# MiniHeating.net
KiCad netlist of a schematic drawn in Altium Designer
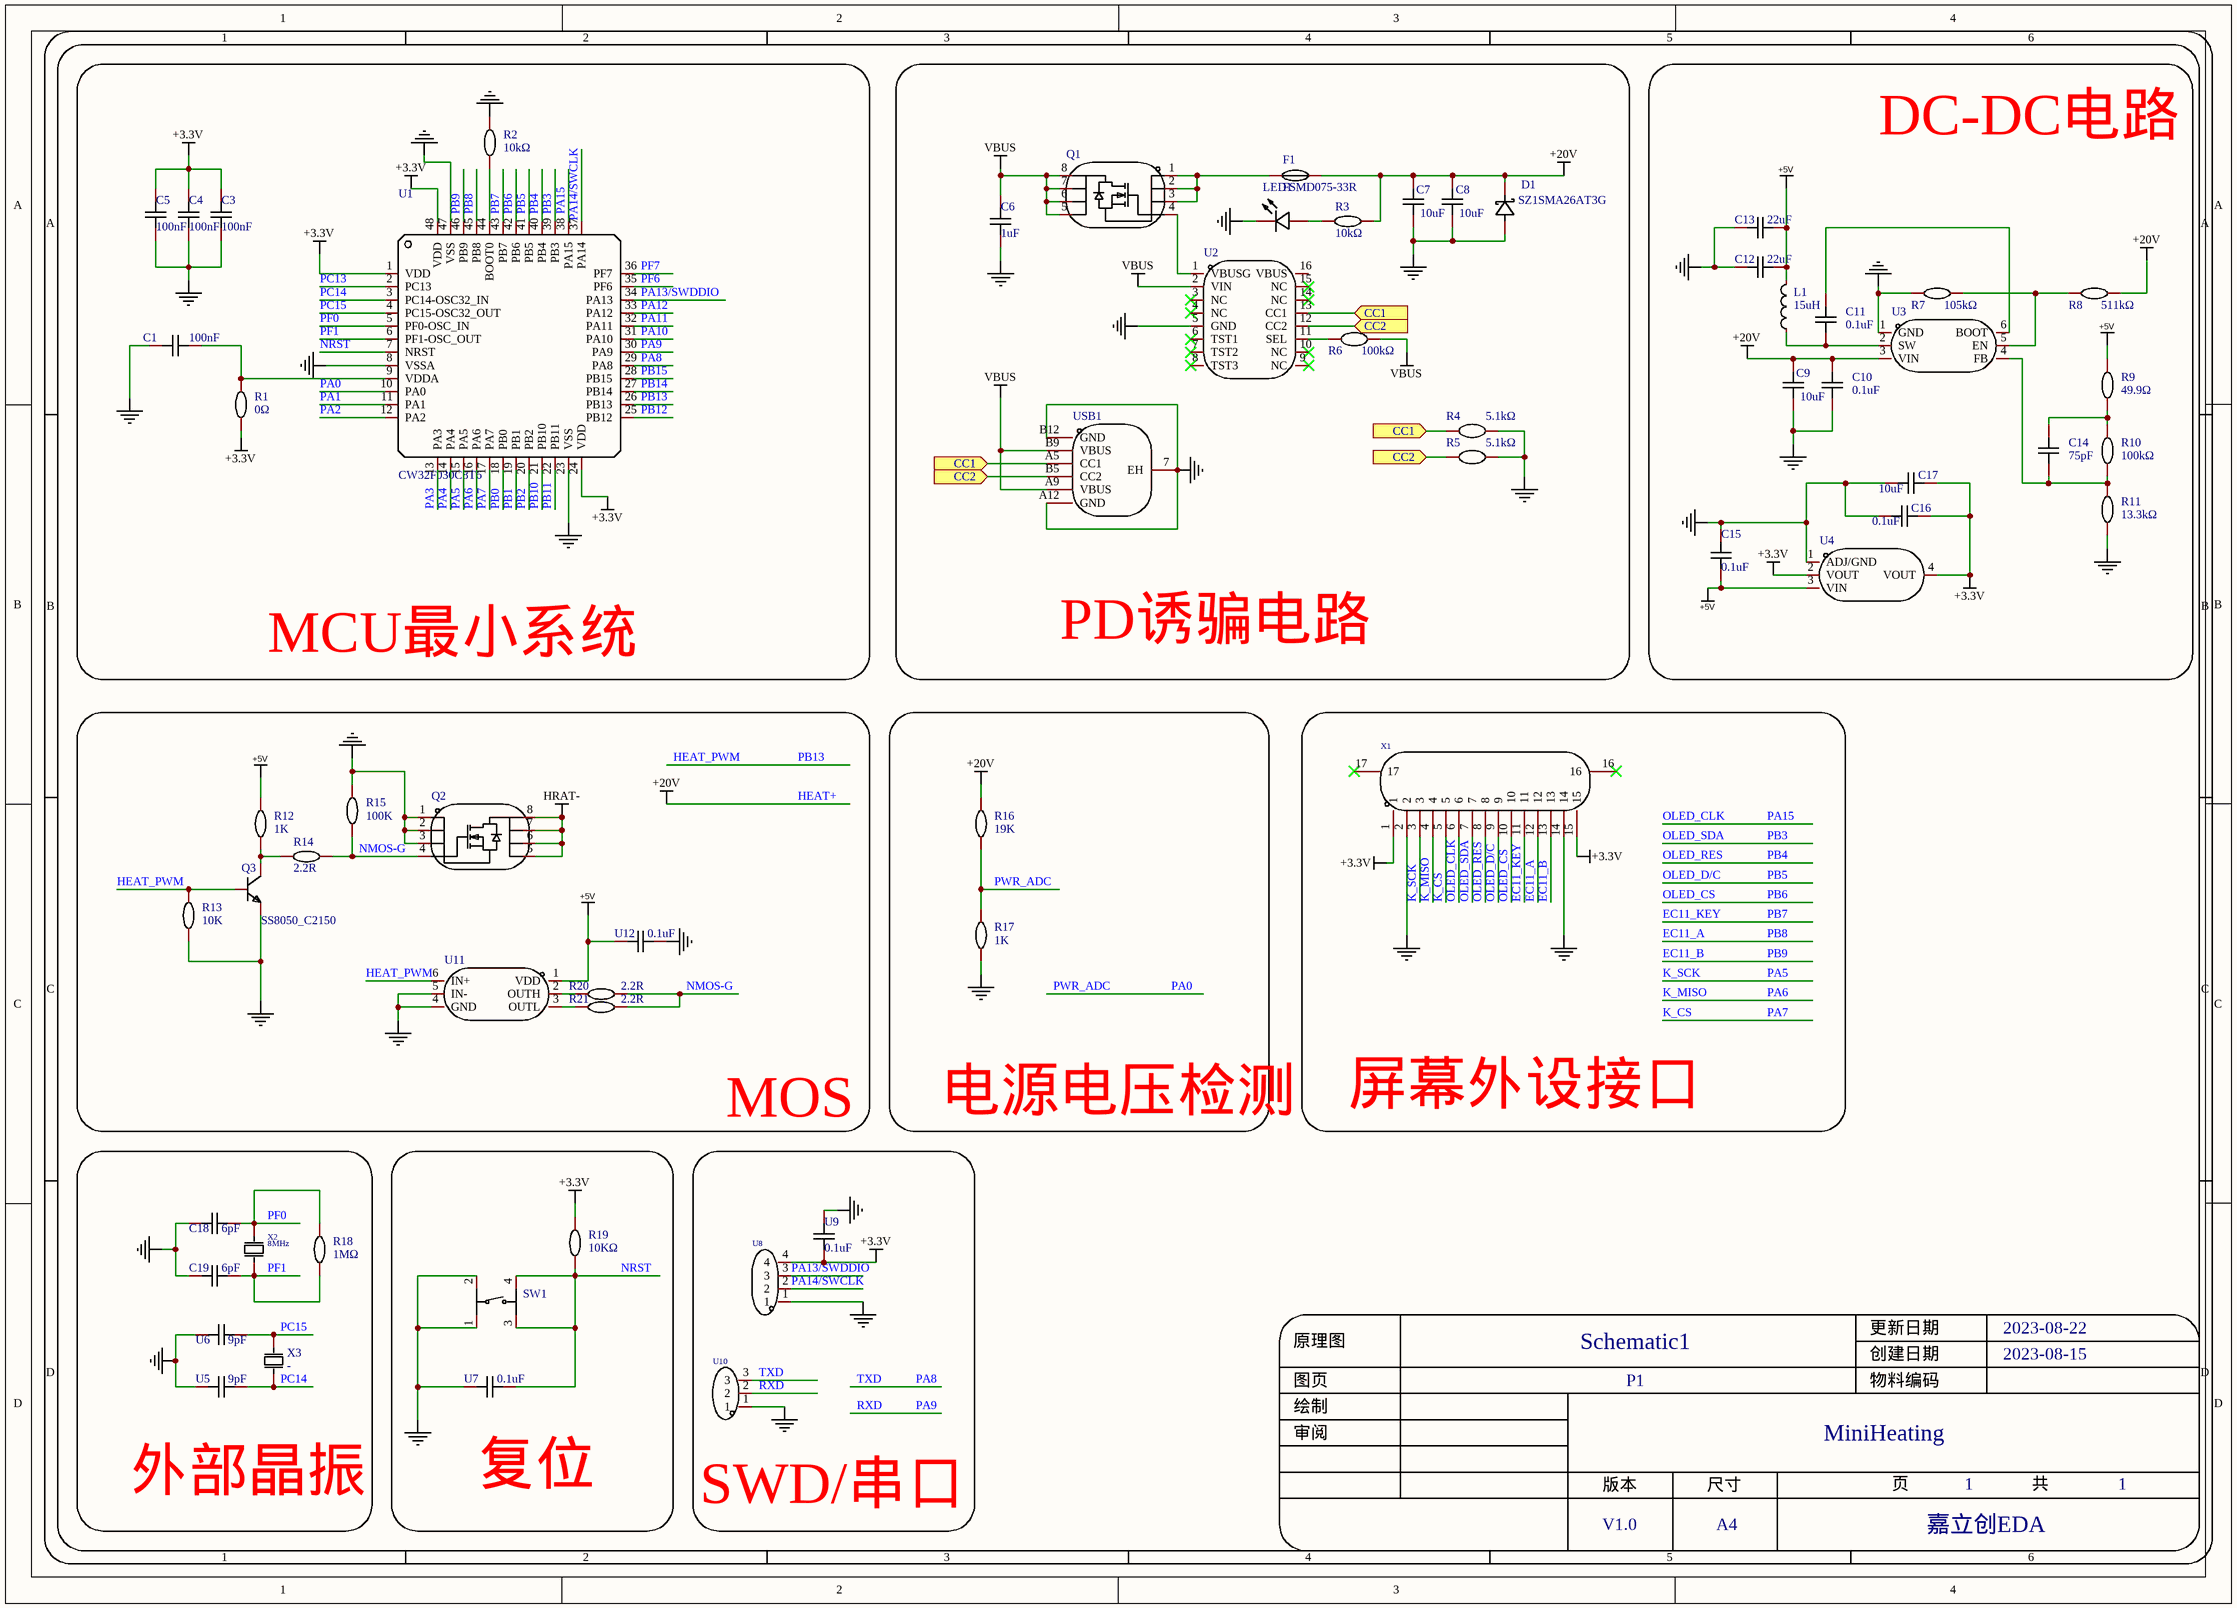
[diagram p0: MiniHeating.SchDoc]

(export (version "E")
  (design (tool "Eeschema 10.0.6"))
  (components
    (comp (ref "C1")
      (value "100nF")
      (footprint "C0603")
      (description "容值:100nF;精度:±10%;额定电压:50V;材质(温度系数):X7R;")
      (fields
        (field (name "MANUFACTURER") "YAGEO(国巨)")
        (field (name "MANUFACTURER PART") "CC0603KRX7R9BB104")
      )
      (libsource (lib "altium-import") (part "root_0_CC0603KRX7R9BB104_"))
    )
    (comp (ref "C3")
      (value "100nF")
      (footprint "C0603")
      (description "容值:100nF;精度:±10%;额定电压:50V;材质(温度系数):X7R;")
      (fields
        (field (name "MANUFACTURER") "YAGEO(国巨)")
        (field (name "MANUFACTURER PART") "CC0603KRX7R9BB104")
      )
      (libsource (lib "altium-import") (part "root_1_CC0603KRX7R9BB104_"))
    )
    (comp (ref "C4")
      (value "100nF")
      (footprint "C0603")
      (description "容值:100nF;精度:±10%;额定电压:50V;材质(温度系数):X7R;")
      (fields
        (field (name "MANUFACTURER") "YAGEO(国巨)")
        (field (name "MANUFACTURER PART") "CC0603KRX7R9BB104")
      )
      (libsource (lib "altium-import") (part "root_1_CC0603KRX7R9BB104_"))
    )
    (comp (ref "C5")
      (value "100nF")
      (footprint "C0603")
      (description "容值:100nF;精度:±10%;额定电压:50V;材质(温度系数):X7R;")
      (fields
        (field (name "MANUFACTURER") "YAGEO(国巨)")
        (field (name "MANUFACTURER PART") "CC0603KRX7R9BB104")
      )
      (libsource (lib "altium-import") (part "root_1_CC0603KRX7R9BB104_"))
    )
    (comp (ref "C6")
      (value "1uF")
      (footprint "C0805")
      (description "容值:10uF;精度:±20%;额定电压:16V;材质(温度系数):-;")
      (fields (field (name "MANUFACTURER") "SAMSUNG(三星)") (field (name "MANUFACTURER PART") "10uF"))
      (libsource (lib "altium-import") (part "root_0_10uF_C15415_"))
    )
    (comp (ref "C7")
      (value "10uF")
      (footprint "C0805")
      (description "容值:10uF;精度:±10%;额定电压:-;材质(温度系数):-;")
      (fields
        (field (name "NAME") "10uF")
        (field (name "MANUFACTURER") "muRata(村田)")
        (field (name "MANUFACTURER PART") "GRT21BC71E106KE13L")
      )
      (libsource (lib "altium-import") (part "root_1_GRT21BC71E106KE13L_"))
    )
    (comp (ref "C8")
      (value "10uF")
      (footprint "C0805")
      (description "容值:10uF;精度:±10%;额定电压:-;材质(温度系数):-;")
      (fields
        (field (name "NAME") "10uF")
        (field (name "MANUFACTURER") "muRata(村田)")
        (field (name "MANUFACTURER PART") "GRT21BC71E106KE13L")
      )
      (libsource (lib "altium-import") (part "root_1_GRT21BC71E106KE13L_"))
    )
    (comp (ref "C9")
      (value "10uF")
      (footprint "C0805")
      (description "容值:10uF;精度:±10%;额定电压:-;材质(温度系数):-;")
      (fields
        (field (name "NAME") "10uF")
        (field (name "MANUFACTURER") "muRata(村田)")
        (field (name "MANUFACTURER PART") "GRT21BC71E106KE13L")
      )
      (libsource (lib "altium-import") (part "root_1_GRT21BC71E106KE13L_"))
    )
    (comp (ref "C10")
      (value "0.1uF")
      (footprint "C0603")
      (description "容值:0.1uF;精度:±10%;额定电压:50V;温度系数:-;")
      (fields
        (field (name "MANUFACTURER") "Knowles(楼氏)")
        (field (name "MANUFACTURER PART") "0603BB104K500NGT")
      )
      (libsource (lib "altium-import") (part "root_1_0603BB104K500NGT_"))
    )
    (comp (ref "C11")
      (value "0.1uF")
      (footprint "C0603")
      (description "容值:0.1uF;精度:±10%;额定电压:50V;温度系数:-;")
      (fields
        (field (name "MANUFACTURER") "Knowles(楼氏)")
        (field (name "MANUFACTURER PART") "0603BB104K500NGT")
      )
      (libsource (lib "altium-import") (part "root_3_0603BB104K500NGT_"))
    )
    (comp (ref "C12")
      (value "22uF")
      (footprint "C0805")
      (description "容值:10uF;精度:±10%;额定电压:-;材质(温度系数):-;")
      (fields
        (field (name "NAME") "22uF")
        (field (name "MANUFACTURER") "muRata(村田)")
        (field (name "MANUFACTURER PART") "GRT21BC71E106KE13L")
      )
      (libsource (lib "altium-import") (part "root_2_GRT21BC71E106KE13L_"))
    )
    (comp (ref "C13")
      (value "22uF")
      (footprint "C0805")
      (description "容值:10uF;精度:±10%;额定电压:-;材质(温度系数):-;")
      (fields
        (field (name "NAME") "22uF")
        (field (name "MANUFACTURER") "muRata(村田)")
        (field (name "MANUFACTURER PART") "GRT21BC71E106KE13L")
      )
      (libsource (lib "altium-import") (part "root_2_GRT21BC71E106KE13L_"))
    )
    (comp (ref "C14")
      (value "75pF")
      (footprint "C0603")
      (description "容值:0.1uF;精度:±10%;额定电压:50V;温度系数:-;")
      (fields
        (field (name "MANUFACTURER") "Knowles(楼氏)")
        (field (name "MANUFACTURER PART") "0603BB104K500NGT")
      )
      (libsource (lib "altium-import") (part "root_1_0603BB104K500NGT_"))
    )
    (comp (ref "C15")
      (value "0.1uF")
      (footprint "C0603")
      (description "容值:0.1uF;精度:±10%;额定电压:50V;温度系数:-;")
      (fields
        (field (name "MANUFACTURER") "Knowles(楼氏)")
        (field (name "MANUFACTURER PART") "0603BB104K500NGT")
      )
      (libsource (lib "altium-import") (part "root_1_0603BB104K500NGT_"))
    )
    (comp (ref "C16")
      (value "0.1uF")
      (footprint "C0603")
      (description "容值:0.1uF;精度:±10%;额定电压:50V;温度系数:-;")
      (fields
        (field (name "MANUFACTURER") "Knowles(楼氏)")
        (field (name "MANUFACTURER PART") "0603BB104K500NGT")
      )
      (libsource (lib "altium-import") (part "root_2_0603BB104K500NGT_"))
    )
    (comp (ref "C17")
      (value "10uF")
      (footprint "C0805")
      (description "容值:10uF;精度:±10%;额定电压:-;材质(温度系数):-;")
      (fields
        (field (name "NAME") "10uF")
        (field (name "MANUFACTURER") "muRata(村田)")
        (field (name "MANUFACTURER PART") "GRT21BC71E106KE13L")
      )
      (libsource (lib "altium-import") (part "root_2_GRT21BC71E106KE13L_"))
    )
    (comp (ref "C18")
      (value "6pF")
      (footprint "C0603")
      (description "容值:6pF;额定电压:50V;材质(温度系数):C0G;")
      (fields (field (name "MANUFACTURER") "TDK") (field (name "MANUFACTURER PART") "CGA3E2C0G1H060DT0Y0N"))
      (libsource (lib "altium-import") (part "root_0_CGA3E2C0G1H060DT0Y0N_"))
    )
    (comp (ref "C19")
      (value "6pF")
      (footprint "C0603")
      (description "容值:6pF;额定电压:50V;材质(温度系数):C0G;")
      (fields (field (name "MANUFACTURER") "TDK") (field (name "MANUFACTURER PART") "CGA3E2C0G1H060DT0Y0N"))
      (libsource (lib "altium-import") (part "root_0_CGA3E2C0G1H060DT0Y0N_"))
    )
    (comp (ref "D1")
      (value "SZ1SMA26AT3G")
      (footprint "SMA_L4.3-W2.6-LS5.2-FD")
      (fields (field (name "NAME") "SZ1SMA26AT3G") (field (name "MANUFACTURER") "Littelfuse(美国力特)"))
      (libsource (lib "altium-import") (part "root_3_SZ1SMA26AT3G_"))
    )
    (comp (ref "F1")
      (value "FSMD075-33R")
      (footprint "F1812")
      (description "最大电压:33V;最大电流:40A;保持电流:750mA;跳闸电流:1.5A;")
      (fields (field (name "NAME") "FSMD075-33R") (field (name "MANUFACTURER") "FUZETEC(台湾富致)"))
      (libsource (lib "altium-import") (part "root_0_FSMD075-33R_"))
    )
    (comp (ref "L1")
      (value "15uH")
      (footprint "IND-SMD_L7.0-W6.6_FXL0630")
      (description "电感值:15uH;精度:±20%;额定电流:3A;饱和电流(Isat):4.5A;")
      (fields (field (name "MANUFACTURER") "cjiang(长江微电)") (field (name "MANUFACTURER PART") "FXL0630-150-M"))
      (libsource (lib "altium-import") (part "root_1_FXL0630-150-M_"))
    )
    (comp (ref "LED1")
      (value "KT-0603R")
      (footprint "LED0603-RD")
      (description "发光颜色:红灯;二极管配置:-;透镜颜色:-;主波长:-;色温:-;功率:-;发光角度:-;安装方式:-;工作温度:-40℃~+85℃;")
      (fields (field (name "MANUFACTURER") "KENTO"))
      (libsource (lib "altium-import") (part "root_0_KT-0603R_"))
    )
    (comp (ref "Q1")
      (value "BSC123N08NS3 G")
      (footprint "PG-TDSON-8_L5.0-W6.0-P1.27-BL-EP")
      (libsource (lib "altium-import") (part "root_0_mirrored_BSC123N08NS3 G_"))
    )
    (comp (ref "Q2")
      (value "BSC123N08NS3 G")
      (footprint "PG-TDSON-8_L5.0-W6.0-P1.27-BL-EP")
      (libsource (lib "altium-import") (part "root_0_BSC123N08NS3 G_"))
    )
    (comp (ref "Q3")
      (value "SS8050_C2150")
      (footprint "SOT-23-3_L2.9-W1.3-P1.90-LS2.4-BR")
      (description "晶体管类型:NPN;集射极击穿电压(Vceo):25V;集电极电流(Ic):1.5A;功率(Pd):300mW;直流电流增益(hFE@Ic,Vce):200@100mA,1V;")
      (fields
        (field (name "DEVICE") "SS8050_C2150")
        (field (name "MANUFACTURER") "CJ(江苏长电/长晶)")
        (field (name "MANUFACTURER PART") "SS8050")
      )
      (libsource (lib "altium-import") (part "root_0_SS8050_C2150_"))
    )
    (comp (ref "R1")
      (value "0Ω")
      (footprint "R0603")
      (description "电阻类型:厚膜电阻;阻值:470kΩ;精度:±1%;功率:100mW;")
      (fields
        (field (name "MANUFACTURER") "UNI-ROYAL(厚声)")
        (field (name "MANUFACTURER PART") "0603WAF4703T5E")
      )
      (libsource (lib "altium-import") (part "root_1_0603WAF4703T5E_"))
    )
    (comp (ref "R2")
      (value "10kΩ")
      (footprint "R0603")
      (description "电阻类型:厚膜电阻;阻值:24kΩ;精度:±1%;功率:100mW;")
      (fields
        (field (name "MANUFACTURER") "UNI-ROYAL(厚声)")
        (field (name "MANUFACTURER PART") "0603WAF2402T5E")
      )
      (libsource (lib "altium-import") (part "root_1_0603WAF2402T5E_"))
    )
    (comp (ref "R3")
      (value "10kΩ")
      (footprint "R0603")
      (description "电阻类型:薄膜电阻;阻值:10kΩ;精度:±0.1%;功率:63mW;")
      (fields
        (field (name "MANUFACTURER") "SEI(Stackpole Electronics Inc.)")
        (field (name "MANUFACTURER PART") "RNCS0603BKE10K0")
      )
      (libsource (lib "altium-import") (part "root_2_RNCS0603BKE10K0_"))
    )
    (comp (ref "R4")
      (value "5.1kΩ")
      (footprint "R0603")
      (description "电阻类型:厚膜电阻;阻值:10kΩ;精度:±0.5%;功率:100mW;")
      (fields (field (name "MANUFACTURER") "YAGEO(国巨)") (field (name "MANUFACTURER PART") "AC0603DR-0710KL"))
      (libsource (lib "altium-import") (part "root_0_AC0603DR-0710KL_"))
    )
    (comp (ref "R5")
      (value "5.1kΩ")
      (footprint "R0603")
      (description "电阻类型:厚膜电阻;阻值:10kΩ;精度:±0.5%;功率:100mW;")
      (fields (field (name "MANUFACTURER") "YAGEO(国巨)") (field (name "MANUFACTURER PART") "AC0603DR-0710KL"))
      (libsource (lib "altium-import") (part "root_0_AC0603DR-0710KL_"))
    )
    (comp (ref "R6")
      (value "100kΩ")
      (footprint "R0603")
      (description "阻值:100kΩ;功率:125mW;")
      (fields
        (field (name "NAME") "100kΩ")
        (field (name "MANUFACTURER") "Milliohm(毫欧)")
        (field (name "MANUFACTURER PART") "HoLTT0805-1/8W-100K-5%")
      )
      (libsource (lib "altium-import") (part "root_0_HoLTT0805-1/8W-100K-5%_"))
    )
    (comp (ref "R7")
      (value "105kΩ")
      (footprint "R0603")
      (description "电阻类型:厚膜电阻;阻值:105kΩ;精度:±1%;功率:100mW;")
      (fields (field (name "MANUFACTURER") "YAGEO(国巨)") (field (name "MANUFACTURER PART") "AC0603FR-07105KL"))
      (libsource (lib "altium-import") (part "root_0_AC0603FR-07105KL_"))
    )
    (comp (ref "R8")
      (value "511kΩ")
      (footprint "R0603")
      (description "电阻类型:厚膜电阻;阻值:105kΩ;精度:±1%;功率:100mW;")
      (fields (field (name "MANUFACTURER") "YAGEO(国巨)") (field (name "MANUFACTURER PART") "AC0603FR-07105KL"))
      (libsource (lib "altium-import") (part "root_0_AC0603FR-07105KL_"))
    )
    (comp (ref "R9")
      (value "49.9Ω")
      (footprint "R0603")
      (description "阻值:50kΩ;精度:±0.1%;功率:62.5mW;")
      (fields (field (name "MANUFACTURER") "Viking(光颉)") (field (name "MANUFACTURER PART") "AR03BTC5002A"))
      (libsource (lib "altium-import") (part "root_1_AR03BTC5002A_"))
    )
    (comp (ref "R10")
      (value "100kΩ")
      (footprint "R0603")
      (description "阻值:50kΩ;精度:±0.1%;功率:62.5mW;")
      (fields (field (name "MANUFACTURER") "Viking(光颉)") (field (name "MANUFACTURER PART") "AR03BTC5002A"))
      (libsource (lib "altium-import") (part "root_1_AR03BTC5002A_"))
    )
    (comp (ref "R11")
      (value "13.3kΩ")
      (footprint "R0603")
      (description "阻值:50kΩ;精度:±0.1%;功率:62.5mW;")
      (fields (field (name "MANUFACTURER") "Viking(光颉)") (field (name "MANUFACTURER PART") "AR03BTC5002A"))
      (libsource (lib "altium-import") (part "root_1_AR03BTC5002A_"))
    )
    (comp (ref "R12")
      (value "1K")
      (footprint "R0603")
      (description "电阻类型:厚膜电阻;阻值:470kΩ;精度:±1%;功率:100mW;")
      (fields
        (field (name "MANUFACTURER") "UNI-ROYAL(厚声)")
        (field (name "MANUFACTURER PART") "0603WAF4703T5E")
      )
      (libsource (lib "altium-import") (part "root_1_0603WAF4703T5E_"))
    )
    (comp (ref "R13")
      (value "10K")
      (footprint "R0603")
      (description "电阻类型:厚膜电阻;阻值:470kΩ;精度:±1%;功率:100mW;")
      (fields
        (field (name "MANUFACTURER") "UNI-ROYAL(厚声)")
        (field (name "MANUFACTURER PART") "0603WAF4703T5E")
      )
      (libsource (lib "altium-import") (part "root_1_0603WAF4703T5E_"))
    )
    (comp (ref "R14")
      (value "2.2R")
      (footprint "R0603")
      (description "电阻类型:厚膜电阻;阻值:470kΩ;精度:±1%;功率:100mW;")
      (fields
        (field (name "MANUFACTURER") "UNI-ROYAL(厚声)")
        (field (name "MANUFACTURER PART") "0603WAF4703T5E")
      )
      (libsource (lib "altium-import") (part "root_2_0603WAF4703T5E_"))
    )
    (comp (ref "R15")
      (value "100K")
      (footprint "R0603")
      (description "电阻类型:厚膜电阻;阻值:470kΩ;精度:±1%;功率:100mW;")
      (fields
        (field (name "MANUFACTURER") "UNI-ROYAL(厚声)")
        (field (name "MANUFACTURER PART") "0603WAF4703T5E")
      )
      (libsource (lib "altium-import") (part "root_1_0603WAF4703T5E_"))
    )
    (comp (ref "R16")
      (value "19K")
      (footprint "R0603")
      (description "电阻类型:厚膜电阻;阻值:470kΩ;精度:±1%;功率:100mW;")
      (fields
        (field (name "MANUFACTURER") "UNI-ROYAL(厚声)")
        (field (name "MANUFACTURER PART") "0603WAF4703T5E")
      )
      (libsource (lib "altium-import") (part "root_1_0603WAF4703T5E_"))
    )
    (comp (ref "R17")
      (value "1K")
      (footprint "R0603")
      (description "电阻类型:厚膜电阻;阻值:470kΩ;精度:±1%;功率:100mW;")
      (fields
        (field (name "MANUFACTURER") "UNI-ROYAL(厚声)")
        (field (name "MANUFACTURER PART") "0603WAF4703T5E")
      )
      (libsource (lib "altium-import") (part "root_1_0603WAF4703T5E_"))
    )
    (comp (ref "R18")
      (value "1MΩ")
      (footprint "R0603")
      (description "电阻类型:厚膜电阻;阻值:1MΩ;精度:±1%;功率:100mW;")
      (fields
        (field (name "MANUFACTURER") "UNI-ROYAL(厚声)")
        (field (name "MANUFACTURER PART") "0603WAF1004T5E")
      )
      (libsource (lib "altium-import") (part "root_1_0603WAF1004T5E_"))
    )
    (comp (ref "R19")
      (value "10KΩ")
      (footprint "R0603")
      (description "电阻类型:厚膜电阻;阻值:1MΩ;精度:±1%;功率:100mW;")
      (fields
        (field (name "MANUFACTURER") "UNI-ROYAL(厚声)")
        (field (name "MANUFACTURER PART") "0603WAF1004T5E")
      )
      (libsource (lib "altium-import") (part "root_1_0603WAF1004T5E_"))
    )
    (comp (ref "R20")
      (value "2.2R")
      (footprint "R0603")
      (description "电阻类型:厚膜电阻;阻值:470kΩ;精度:±1%;功率:100mW;")
      (fields
        (field (name "MANUFACTURER") "UNI-ROYAL(厚声)")
        (field (name "MANUFACTURER PART") "0603WAF4703T5E")
      )
      (libsource (lib "altium-import") (part "root_2_0603WAF4703T5E_"))
    )
    (comp (ref "R21")
      (value "2.2R")
      (footprint "R0603")
      (description "电阻类型:厚膜电阻;阻值:470kΩ;精度:±1%;功率:100mW;")
      (fields
        (field (name "MANUFACTURER") "UNI-ROYAL(厚声)")
        (field (name "MANUFACTURER PART") "0603WAF4703T5E")
      )
      (libsource (lib "altium-import") (part "root_2_0603WAF4703T5E_"))
    )
    (comp (ref "SW1")
      (value "TS-1186D-C-A")
      (footprint "SW-SMD_TS-1186D-C-A")
      (description "触点电流:50mA;额定电压(DC):12V;绝缘电阻:-;电路结构:单刀单掷;安装方式:卧贴;带灯:无;作用力:260gf;机械寿命:10万次;带支架:否;")
      (fields (field (name "MANUFACTURER") "XKB Connectivity(中国星坤)"))
      (libsource (lib "altium-import") (part "root_1_TS-1186D-C-A_"))
    )
    (comp (ref "U1")
      (value "CW32F030C8T6")
      (footprint "LQFP-48_L7.0-W7.0-P0.50-LS9.0-TL")
      (fields (field (name "NAME") "CW32F030C8T6") (field (name "MANUFACTURER") "CW(芯源)"))
      (libsource (lib "altium-import") (part "root_0_CW32F030C8T6_C3019113_"))
    )
    (comp (ref "U2")
      (value "IP2721")
      (footprint "TSSOP-16_L5.0-W4.4-P0.65-LS6.4-BL")
      (fields (field (name "MANUFACTURER") "INJOINIC(英集芯)"))
      (libsource (lib "altium-import") (part "root_0_IP2721_"))
    )
    (comp (ref "U3")
      (value "TPS54202DDCR")
      (footprint "SOT-23-6_L2.9-W1.6-P0.95-LS2.8-BL")
      (description "可输出电流:2A;开关工作频率:500kHz;输出类型:Adjustable;输出电压的路数:1;功能类型:Step-Down;输出配置:Positive;")
      (fields (field (name "MANUFACTURER") "TI(德州仪器)"))
      (libsource (lib "altium-import") (part "root_0_TPS54202DDCR_"))
    )
    (comp (ref "U4")
      (value "LM1117GS-3.3")
      (footprint "SOT-223-3_L6.5-W3.4-P2.30-LS7.0-BR")
      (description "输出类型:-;")
      (fields (field (name "MANUFACTURER") "HTC"))
      (libsource (lib "altium-import") (part "root_0_LM1117GS-3.3_"))
    )
    (comp (ref "U5")
      (value "9pF")
      (footprint "C0603")
      (description "容值:9pF;额定电压:50V;材质(温度系数):C0G;")
      (fields (field (name "MANUFACTURER") "TDK") (field (name "MANUFACTURER PART") "C1608C0G1H090D080AA"))
      (libsource (lib "altium-import") (part "root_0_C1608C0G1H090D080AA_"))
    )
    (comp (ref "U6")
      (value "9pF")
      (footprint "C0603")
      (description "容值:9pF;额定电压:50V;材质(温度系数):C0G;")
      (fields (field (name "MANUFACTURER") "TDK") (field (name "MANUFACTURER PART") "C1608C0G1H090D080AA"))
      (libsource (lib "altium-import") (part "root_0_C1608C0G1H090D080AA_"))
    )
    (comp (ref "U7")
      (value "0.1uF")
      (footprint "C0603")
      (description "容值:9pF;额定电压:50V;材质(温度系数):C0G;")
      (fields (field (name "MANUFACTURER") "TDK") (field (name "MANUFACTURER PART") "C1608C0G1H090D080AA"))
      (libsource (lib "altium-import") (part "root_0_C1608C0G1H090D080AA_"))
    )
    (comp (ref "U8")
      (value "ZX-PZ2.54-1-4PWZ")
      (footprint "HDR-TH_4P-P2.54-H-M-W10.3")
      (fields (field (name "MANUFACTURER") "Megastar(兆星)"))
      (libsource (lib "altium-import") (part "root_2_ZX-PZ2.54-1-4PWZ_"))
    )
    (comp (ref "U9")
      (value "0.1uF")
      (footprint "C0603")
      (description "容值:9pF;额定电压:50V;材质(温度系数):C0G;")
      (fields (field (name "MANUFACTURER") "TDK") (field (name "MANUFACTURER PART") "C1608C0G1H090D080AA"))
      (libsource (lib "altium-import") (part "root_1_C1608C0G1H090D080AA_"))
    )
    (comp (ref "U10")
      (value "ZX-PZ2.54-1-3PZZ")
      (footprint "HDR-TH_3P-P2.54-V-M-1")
      (fields (field (name "MANUFACTURER") "Megastar(兆星)"))
      (libsource (lib "altium-import") (part "root_2_ZX-PZ2.54-1-3PZZ_"))
    )
    (comp (ref "U11")
      (value "UCC27511DBVR")
      (footprint "SOT-23-6_L2.9-W1.6-P0.95-LS2.8-BL")
      (description "驱动配置:低边;负载类型:MOSFET；IGBT;电源电压:4.5V~18V;峰值灌电流:8A;峰值拉电流:4A;")
      (fields (field (name "MANUFACTURER") "TI(德州仪器)"))
      (libsource (lib "altium-import") (part "root_0_mirrored_UCC27511DBVR_"))
    )
    (comp (ref "U12")
      (value "0.1uF")
      (footprint "C0603")
      (description "容值:9pF;额定电压:50V;材质(温度系数):C0G;")
      (fields (field (name "MANUFACTURER") "TDK") (field (name "MANUFACTURER PART") "C1608C0G1H090D080AA"))
      (libsource (lib "altium-import") (part "root_0_C1608C0G1H090D080AA_"))
    )
    (comp (ref "USB1")
      (value "TYPE-C-6P-DIP2X2")
      (footprint "TYPE-C-SMD_TYPE-C-6P")
      (libsource (lib "altium-import") (part "root_0_TYPE-C-6P-DIP2X2_"))
    )
    (comp (ref "X1")
      (value "AFC01-S15FCA-00")
      (footprint "FPC-SMD_15P-P0.50_JS_AFC01-S15FCA-00")
      (description "间距:0.5mm;触点数量:15;锁定特性:翻盖式;安装类型:卧贴;触点类型:下接;工作温度范围:-;")
      (fields (field (name "MANUFACTURER") "JS(钜硕电子)"))
      (libsource (lib "altium-import") (part "root_1_AFC01-S15FCA-00_"))
    )
    (comp (ref "X2")
      (value "8MHz")
      (footprint "HC-49US_L11.5-W4.5-P4.88")
      (description "频率:8MHz;频率公差:±30ppm;负载电容:20pF;")
      (fields (field (name "MANUFACTURER") "TAE(雅晶鑫)") (field (name "MANUFACTURER PART") "TAXD8M2GLFBET2T"))
      (libsource (lib "altium-import") (part "root_1_TAXD8M2GLFBET2T_"))
    )
    (comp (ref "X3")
      (value "-")
      (footprint "OSC-SMD_L3.2-W1.5")
      (description "频率:-;负载电容:-;")
      (fields (field (name "MANUFACTURER") "TKD(泰晶)") (field (name "MANUFACTURER PART") "SF32WK32768D31T002"))
      (libsource (lib "altium-import") (part "root_1_SF32WK32768D31T002_"))
    )
  )
  (nets
    (net (code "1") (name "+3.3V") (class "Default")
      (node (ref "C16") (pin "1") (pinfunction "1_1") (pintype "passive"))
      (node (ref "C17") (pin "1") (pinfunction "1_1") (pintype "passive"))
      (node (ref "C3") (pin "2") (pinfunction "2_2") (pintype "passive"))
      (node (ref "C4") (pin "2") (pinfunction "2_2") (pintype "passive"))
      (node (ref "C5") (pin "2") (pinfunction "2_2") (pintype "passive"))
      (node (ref "R1") (pin "1") (pinfunction "1_1") (pintype "passive"))
      (node (ref "R19") (pin "2") (pinfunction "2_2") (pintype "passive"))
      (node (ref "U1") (pin "1") (pinfunction "VDD_1") (pintype "passive"))
      (node (ref "U1") (pin "24") (pinfunction "VDD_24") (pintype "passive"))
      (node (ref "U1") (pin "48") (pinfunction "VDD_48") (pintype "passive"))
      (node (ref "U4") (pin "2") (pinfunction "VOUT_2") (pintype "passive"))
      (node (ref "U4") (pin "4") (pinfunction "VOUT_4") (pintype "passive"))
      (node (ref "U8") (pin "4") (pinfunction "4_4") (pintype "passive"))
      (node (ref "U9") (pin "1") (pinfunction "1_1") (pintype "passive"))
      (node (ref "X1") (pin "1") (pinfunction "1_1") (pintype "passive"))
      (node (ref "X1") (pin "15") (pinfunction "15_15") (pintype "passive"))
    )
    (net (code "2") (name "+5V") (class "Default")
      (node (ref "C12") (pin "1") (pinfunction "1_1") (pintype "passive"))
      (node (ref "C13") (pin "1") (pinfunction "1_1") (pintype "passive"))
      (node (ref "C15") (pin "1") (pinfunction "1_1") (pintype "passive"))
      (node (ref "L1") (pin "2") (pinfunction "2_2") (pintype "passive"))
      (node (ref "R12") (pin "2") (pinfunction "2_2") (pintype "passive"))
      (node (ref "R9") (pin "2") (pinfunction "2_2") (pintype "passive"))
      (node (ref "U11") (pin "1") (pinfunction "VDD_1") (pintype "passive"))
      (node (ref "U12") (pin "1") (pinfunction "1_1") (pintype "passive"))
      (node (ref "U4") (pin "3") (pinfunction "VIN_3") (pintype "passive"))
    )
    (net (code "3") (name "+20V") (class "Default")
      (node (ref "C10") (pin "2") (pinfunction "2_2") (pintype "passive"))
      (node (ref "C7") (pin "2") (pinfunction "2_2") (pintype "passive"))
      (node (ref "C8") (pin "2") (pinfunction "2_2") (pintype "passive"))
      (node (ref "C9") (pin "2") (pinfunction "2_2") (pintype "passive"))
      (node (ref "D1") (pin "2") (pinfunction "K_2") (pintype "passive"))
      (node (ref "F1") (pin "2") (pinfunction "2_2") (pintype "passive"))
      (node (ref "R16") (pin "2") (pinfunction "2_2") (pintype "passive"))
      (node (ref "R3") (pin "1") (pinfunction "1_1") (pintype "passive"))
      (node (ref "R8") (pin "2") (pinfunction "2_2") (pintype "passive"))
      (node (ref "U3") (pin "3") (pinfunction "VIN_3") (pintype "passive"))
    )
    (net (code "4") (name "/CC1") (class "Default")
      (node (ref "R4") (pin "1") (pinfunction "1_1") (pintype "passive"))
      (node (ref "U2") (pin "13") (pinfunction "CC1_13") (pintype "passive"))
      (node (ref "USB1") (pin "A5") (pinfunction "CC1_A5") (pintype "passive"))
    )
    (net (code "5") (name "/CC2") (class "Default")
      (node (ref "R5") (pin "1") (pinfunction "1_1") (pintype "passive"))
      (node (ref "U2") (pin "12") (pinfunction "CC2_12") (pintype "passive"))
      (node (ref "USB1") (pin "B5") (pinfunction "CC2_B5") (pintype "passive"))
    )
    (net (code "6") (name "/EC11_A") (class "Default")
      (node (ref "U1") (pin "45") (pinfunction "PB8_45") (pintype "passive"))
      (node (ref "X1") (pin "12") (pinfunction "12_12") (pintype "passive"))
    )
    (net (code "7") (name "/EC11_B") (class "Default")
      (node (ref "U1") (pin "46") (pinfunction "PB9_46") (pintype "passive"))
      (node (ref "X1") (pin "13") (pinfunction "13_13") (pintype "passive"))
    )
    (net (code "8") (name "/EC11_KEY") (class "Default")
      (node (ref "U1") (pin "43") (pinfunction "PB7_43") (pintype "passive"))
      (node (ref "X1") (pin "11") (pinfunction "11_11") (pintype "passive"))
    )
    (net (code "9") (name "/HEAT_PWM") (class "Default")
      (node (ref "Q3") (pin "1") (pinfunction "B_1") (pintype "passive"))
      (node (ref "R13") (pin "2") (pinfunction "2_2") (pintype "passive"))
      (node (ref "U1") (pin "26") (pinfunction "PB13_26") (pintype "passive"))
      (node (ref "U11") (pin "6") (pinfunction "IN+_6") (pintype "passive"))
    )
    (net (code "10") (name "/K_CS") (class "Default")
      (node (ref "U1") (pin "17") (pinfunction "PA7_17") (pintype "passive"))
      (node (ref "X1") (pin "5") (pinfunction "5_5") (pintype "passive"))
    )
    (net (code "11") (name "/K_MISO") (class "Default")
      (node (ref "U1") (pin "16") (pinfunction "PA6_16") (pintype "passive"))
      (node (ref "X1") (pin "4") (pinfunction "4_4") (pintype "passive"))
    )
    (net (code "12") (name "/K_SCK") (class "Default")
      (node (ref "U1") (pin "15") (pinfunction "PA5_15") (pintype "passive"))
      (node (ref "X1") (pin "3") (pinfunction "3_3") (pintype "passive"))
    )
    (net (code "13") (name "/NMOS-G") (class "Default")
      (node (ref "Q2") (pin "4") (pinfunction "G_4") (pintype "passive"))
      (node (ref "R14") (pin "1") (pinfunction "1_1") (pintype "passive"))
      (node (ref "R15") (pin "1") (pinfunction "1_1") (pintype "passive"))
      (node (ref "R20") (pin "1") (pinfunction "1_1") (pintype "passive"))
      (node (ref "R21") (pin "1") (pinfunction "1_1") (pintype "passive"))
    )
    (net (code "14") (name "/NRST") (class "Default")
      (node (ref "R19") (pin "1") (pinfunction "1_1") (pintype "passive"))
      (node (ref "SW1") (pin "3") (pinfunction "3_3") (pintype "passive"))
      (node (ref "SW1") (pin "4") (pinfunction "4_4") (pintype "passive"))
      (node (ref "U1") (pin "7") (pinfunction "NRST_7") (pintype "passive"))
      (node (ref "U7") (pin "2") (pinfunction "2_2") (pintype "passive"))
    )
    (net (code "15") (name "/OLED_CLK") (class "Default")
      (node (ref "U1") (pin "38") (pinfunction "PA15_38") (pintype "passive"))
      (node (ref "X1") (pin "6") (pinfunction "6_6") (pintype "passive"))
    )
    (net (code "16") (name "/OLED_CS") (class "Default")
      (node (ref "U1") (pin "42") (pinfunction "PB6_42") (pintype "passive"))
      (node (ref "X1") (pin "10") (pinfunction "10_10") (pintype "passive"))
    )
    (net (code "17") (name "/OLED_D{slash}C") (class "Default")
      (node (ref "U1") (pin "41") (pinfunction "PB5_41") (pintype "passive"))
      (node (ref "X1") (pin "9") (pinfunction "9_9") (pintype "passive"))
    )
    (net (code "18") (name "/OLED_RES") (class "Default")
      (node (ref "U1") (pin "40") (pinfunction "PB4_40") (pintype "passive"))
      (node (ref "X1") (pin "8") (pinfunction "8_8") (pintype "passive"))
    )
    (net (code "19") (name "/OLED_SDA") (class "Default")
      (node (ref "U1") (pin "39") (pinfunction "PB3_39") (pintype "passive"))
      (node (ref "X1") (pin "7") (pinfunction "7_7") (pintype "passive"))
    )
    (net (code "20") (name "/PA0") (class "Default")
      (node (ref "R16") (pin "1") (pinfunction "1_1") (pintype "passive"))
      (node (ref "R17") (pin "2") (pinfunction "2_2") (pintype "passive"))
      (node (ref "U1") (pin "10") (pinfunction "PA0_10") (pintype "passive"))
    )
    (net (code "21") (name "/PA1") (class "Default")
      (node (ref "U1") (pin "11") (pinfunction "PA1_11") (pintype "passive"))
    )
    (net (code "22") (name "/PA2") (class "Default")
      (node (ref "U1") (pin "12") (pinfunction "PA2_12") (pintype "passive"))
    )
    (net (code "23") (name "/PA3") (class "Default")
      (node (ref "U1") (pin "13") (pinfunction "PA3_13") (pintype "passive"))
    )
    (net (code "24") (name "/PA4") (class "Default")
      (node (ref "U1") (pin "14") (pinfunction "PA4_14") (pintype "passive"))
    )
    (net (code "25") (name "/PA8") (class "Default")
      (node (ref "U1") (pin "29") (pinfunction "PA8_29") (pintype "passive"))
      (node (ref "U10") (pin "3") (pinfunction "3_3") (pintype "passive"))
    )
    (net (code "26") (name "/PA9") (class "Default")
      (node (ref "U1") (pin "30") (pinfunction "PA9_30") (pintype "passive"))
      (node (ref "U10") (pin "2") (pinfunction "2_2") (pintype "passive"))
    )
    (net (code "27") (name "/PA10") (class "Default")
      (node (ref "U1") (pin "31") (pinfunction "PA10_31") (pintype "passive"))
    )
    (net (code "28") (name "/PA11") (class "Default")
      (node (ref "U1") (pin "32") (pinfunction "PA11_32") (pintype "passive"))
    )
    (net (code "29") (name "/PA12") (class "Default")
      (node (ref "U1") (pin "33") (pinfunction "PA12_33") (pintype "passive"))
    )
    (net (code "30") (name "/PA13{slash}SWDDIO") (class "Default")
      (node (ref "U1") (pin "34") (pinfunction "PA13_34") (pintype "passive"))
      (node (ref "U8") (pin "3") (pinfunction "3_3") (pintype "passive"))
    )
    (net (code "31") (name "/PA14{slash}SWCLK") (class "Default")
      (node (ref "U1") (pin "37") (pinfunction "PA14_37") (pintype "passive"))
      (node (ref "U8") (pin "2") (pinfunction "2_2") (pintype "passive"))
    )
    (net (code "32") (name "/PB0") (class "Default")
      (node (ref "U1") (pin "18") (pinfunction "PB0_18") (pintype "passive"))
    )
    (net (code "33") (name "/PB1") (class "Default")
      (node (ref "U1") (pin "19") (pinfunction "PB1_19") (pintype "passive"))
    )
    (net (code "34") (name "/PB2") (class "Default")
      (node (ref "U1") (pin "20") (pinfunction "PB2_20") (pintype "passive"))
    )
    (net (code "35") (name "/PB10") (class "Default")
      (node (ref "U1") (pin "21") (pinfunction "PB10_21") (pintype "passive"))
    )
    (net (code "36") (name "/PB11") (class "Default")
      (node (ref "U1") (pin "22") (pinfunction "PB11_22") (pintype "passive"))
    )
    (net (code "37") (name "/PB12") (class "Default")
      (node (ref "U1") (pin "25") (pinfunction "PB12_25") (pintype "passive"))
    )
    (net (code "38") (name "/PB14") (class "Default")
      (node (ref "U1") (pin "27") (pinfunction "PB14_27") (pintype "passive"))
    )
    (net (code "39") (name "/PB15") (class "Default")
      (node (ref "U1") (pin "28") (pinfunction "PB15_28") (pintype "passive"))
    )
    (net (code "40") (name "/PC13") (class "Default")
      (node (ref "U1") (pin "2") (pinfunction "PC13_2") (pintype "passive"))
    )
    (net (code "41") (name "/PC14") (class "Default")
      (node (ref "U1") (pin "3") (pinfunction "PC14-OSC32_IN_3") (pintype "passive"))
      (node (ref "U5") (pin "2") (pinfunction "2_2") (pintype "passive"))
      (node (ref "X3") (pin "1") (pinfunction "OSC1_1") (pintype "passive"))
    )
    (net (code "42") (name "/PC15") (class "Default")
      (node (ref "U1") (pin "4") (pinfunction "PC15-OSC32_OUT_4") (pintype "passive"))
      (node (ref "U6") (pin "2") (pinfunction "2_2") (pintype "passive"))
      (node (ref "X3") (pin "2") (pinfunction "OSC2_2") (pintype "passive"))
    )
    (net (code "43") (name "/PF0") (class "Default")
      (node (ref "C18") (pin "2") (pinfunction "2_2") (pintype "passive"))
      (node (ref "R18") (pin "2") (pinfunction "2_2") (pintype "passive"))
      (node (ref "U1") (pin "5") (pinfunction "PF0-OSC_IN_5") (pintype "passive"))
      (node (ref "X2") (pin "2") (pinfunction "OSC2_2") (pintype "passive"))
    )
    (net (code "44") (name "/PF1") (class "Default")
      (node (ref "C19") (pin "2") (pinfunction "2_2") (pintype "passive"))
      (node (ref "R18") (pin "1") (pinfunction "1_1") (pintype "passive"))
      (node (ref "U1") (pin "6") (pinfunction "PF1-OSC_OUT_6") (pintype "passive"))
      (node (ref "X2") (pin "1") (pinfunction "OSC1_1") (pintype "passive"))
    )
    (net (code "45") (name "/PF6") (class "Default")
      (node (ref "U1") (pin "35") (pinfunction "PF6_35") (pintype "passive"))
    )
    (net (code "46") (name "/PF7") (class "Default")
      (node (ref "U1") (pin "36") (pinfunction "PF7_36") (pintype "passive"))
    )
    (net (code "47") (name "<NO NET>") (class "Default")
      (node (ref "C1") (pin "1") (pinfunction "1_1") (pintype "passive"))
      (node (ref "C10") (pin "1") (pinfunction "1_1") (pintype "passive"))
      (node (ref "C12") (pin "2") (pinfunction "2_2") (pintype "passive"))
      (node (ref "C13") (pin "2") (pinfunction "2_2") (pintype "passive"))
      (node (ref "C15") (pin "2") (pinfunction "2_2") (pintype "passive"))
      (node (ref "C16") (pin "2") (pinfunction "2_2") (pintype "passive"))
      (node (ref "C17") (pin "2") (pinfunction "2_2") (pintype "passive"))
      (node (ref "C18") (pin "1") (pinfunction "1_1") (pintype "passive"))
      (node (ref "C19") (pin "1") (pinfunction "1_1") (pintype "passive"))
      (node (ref "C3") (pin "1") (pinfunction "1_1") (pintype "passive"))
      (node (ref "C4") (pin "1") (pinfunction "1_1") (pintype "passive"))
      (node (ref "C5") (pin "1") (pinfunction "1_1") (pintype "passive"))
      (node (ref "C6") (pin "1") (pinfunction "1_1") (pintype "passive"))
      (node (ref "C7") (pin "1") (pinfunction "1_1") (pintype "passive"))
      (node (ref "C8") (pin "1") (pinfunction "1_1") (pintype "passive"))
      (node (ref "C9") (pin "1") (pinfunction "1_1") (pintype "passive"))
      (node (ref "D1") (pin "1") (pinfunction "A_1") (pintype "passive"))
      (node (ref "LED1") (pin "1") (pinfunction "K_1") (pintype "passive"))
      (node (ref "Q2") (pin "1") (pinfunction "S_1") (pintype "passive"))
      (node (ref "Q2") (pin "2") (pinfunction "S_2") (pintype "passive"))
      (node (ref "Q2") (pin "3") (pinfunction "S_3") (pintype "passive"))
      (node (ref "Q3") (pin "2") (pinfunction "E_2") (pintype "passive"))
      (node (ref "R11") (pin "1") (pinfunction "1_1") (pintype "passive"))
      (node (ref "R13") (pin "1") (pinfunction "1_1") (pintype "passive"))
      (node (ref "R15") (pin "2") (pinfunction "2_2") (pintype "passive"))
      (node (ref "R17") (pin "1") (pinfunction "1_1") (pintype "passive"))
      (node (ref "R2") (pin "2") (pinfunction "2_2") (pintype "passive"))
      (node (ref "R4") (pin "2") (pinfunction "2_2") (pintype "passive"))
      (node (ref "R5") (pin "2") (pinfunction "2_2") (pintype "passive"))
      (node (ref "R7") (pin "1") (pinfunction "1_1") (pintype "passive"))
      (node (ref "SW1") (pin "1") (pinfunction "1_1") (pintype "passive"))
      (node (ref "SW1") (pin "2") (pinfunction "2_2") (pintype "passive"))
      (node (ref "U1") (pin "23") (pinfunction "VSS_23") (pintype "passive"))
      (node (ref "U1") (pin "47") (pinfunction "VSS_47") (pintype "passive"))
      (node (ref "U1") (pin "8") (pinfunction "VSSA_8") (pintype "passive"))
      (node (ref "U10") (pin "1") (pinfunction "1_1") (pintype "passive"))
      (node (ref "U11") (pin "4") (pinfunction "GND_4") (pintype "passive"))
      (node (ref "U11") (pin "5") (pinfunction "IN-_5") (pintype "passive"))
      (node (ref "U12") (pin "2") (pinfunction "2_2") (pintype "passive"))
      (node (ref "U2") (pin "5") (pinfunction "GND_5") (pintype "passive"))
      (node (ref "U3") (pin "1") (pinfunction "GND_1") (pintype "passive"))
      (node (ref "U4") (pin "1") (pinfunction "ADJ/GND_1") (pintype "passive"))
      (node (ref "U5") (pin "1") (pinfunction "1_1") (pintype "passive"))
      (node (ref "U6") (pin "1") (pinfunction "1_1") (pintype "passive"))
      (node (ref "U7") (pin "1") (pinfunction "1_1") (pintype "passive"))
      (node (ref "U8") (pin "1") (pinfunction "1_1") (pintype "passive"))
      (node (ref "U9") (pin "2") (pinfunction "2_2") (pintype "passive"))
      (node (ref "USB1") (pin "7") (pinfunction "EH_7") (pintype "passive"))
      (node (ref "USB1") (pin "A12") (pinfunction "GND_A12") (pintype "passive"))
      (node (ref "USB1") (pin "B12") (pinfunction "GND_B12") (pintype "passive"))
      (node (ref "X1") (pin "14") (pinfunction "14_14") (pintype "passive"))
      (node (ref "X1") (pin "2") (pinfunction "2_2") (pintype "passive"))
    )
    (net (code "48") (name "HRAT-") (class "Default")
      (node (ref "Q2") (pin "5") (pinfunction "D_5") (pintype "passive"))
      (node (ref "Q2") (pin "6") (pinfunction "D_6") (pintype "passive"))
      (node (ref "Q2") (pin "7") (pinfunction "D_7") (pintype "passive"))
      (node (ref "Q2") (pin "8") (pinfunction "D_8") (pintype "passive"))
    )
    (net (code "49") (name "Net-(C14-Pad2)") (class "Default")
      (node (ref "C14") (pin "2") (pinfunction "2_2") (pintype "passive"))
      (node (ref "R10") (pin "2") (pinfunction "2_2") (pintype "passive"))
      (node (ref "R9") (pin "1") (pinfunction "1_1") (pintype "passive"))
    )
    (net (code "50") (name "Net-(F1-Pad1)") (class "Default")
      (node (ref "F1") (pin "1") (pinfunction "1_1") (pintype "passive"))
      (node (ref "Q1") (pin "1") (pinfunction "S_1") (pintype "passive"))
      (node (ref "Q1") (pin "2") (pinfunction "S_2") (pintype "passive"))
      (node (ref "Q1") (pin "3") (pinfunction "S_3") (pintype "passive"))
    )
    (net (code "51") (name "Net-(LED1-A)") (class "Default")
      (node (ref "LED1") (pin "2") (pinfunction "A_2") (pintype "passive"))
      (node (ref "R3") (pin "2") (pinfunction "2_2") (pintype "passive"))
    )
    (net (code "52") (name "Net-(Q1-G)") (class "Default")
      (node (ref "Q1") (pin "4") (pinfunction "G_4") (pintype "passive"))
      (node (ref "U2") (pin "1") (pinfunction "VBUSG_1") (pintype "passive"))
    )
    (net (code "53") (name "Net-(Q3-C)") (class "Default")
      (node (ref "Q3") (pin "3") (pinfunction "C_3") (pintype "passive"))
      (node (ref "R12") (pin "1") (pinfunction "1_1") (pintype "passive"))
      (node (ref "R14") (pin "2") (pinfunction "2_2") (pintype "passive"))
    )
    (net (code "54") (name "Net-(U1-BOOT0)") (class "Default")
      (node (ref "R2") (pin "1") (pinfunction "1_1") (pintype "passive"))
      (node (ref "U1") (pin "44") (pinfunction "BOOT0_44") (pintype "passive"))
    )
    (net (code "55") (name "Net-(U1-VDDA)") (class "Default")
      (node (ref "C1") (pin "2") (pinfunction "2_2") (pintype "passive"))
      (node (ref "R1") (pin "2") (pinfunction "2_2") (pintype "passive"))
      (node (ref "U1") (pin "9") (pinfunction "VDDA_9") (pintype "passive"))
    )
    (net (code "56") (name "Net-(U2-SEL)") (class "Default")
      (node (ref "R6") (pin "1") (pinfunction "1_1") (pintype "passive"))
      (node (ref "U2") (pin "11") (pinfunction "SEL_11") (pintype "passive"))
    )
    (net (code "57") (name "Net-(U3-BOOT)") (class "Default")
      (node (ref "C11") (pin "1") (pinfunction "1_1") (pintype "passive"))
      (node (ref "U3") (pin "6") (pinfunction "BOOT_6") (pintype "passive"))
    )
    (net (code "58") (name "Net-(U3-EN)") (class "Default")
      (node (ref "R7") (pin "2") (pinfunction "2_2") (pintype "passive"))
      (node (ref "R8") (pin "1") (pinfunction "1_1") (pintype "passive"))
      (node (ref "U3") (pin "5") (pinfunction "EN_5") (pintype "passive"))
    )
    (net (code "59") (name "Net-(U3-FB)") (class "Default")
      (node (ref "C14") (pin "1") (pinfunction "1_1") (pintype "passive"))
      (node (ref "R10") (pin "1") (pinfunction "1_1") (pintype "passive"))
      (node (ref "R11") (pin "2") (pinfunction "2_2") (pintype "passive"))
      (node (ref "U3") (pin "4") (pinfunction "FB_4") (pintype "passive"))
    )
    (net (code "60") (name "Net-(U3-SW)") (class "Default")
      (node (ref "C11") (pin "2") (pinfunction "2_2") (pintype "passive"))
      (node (ref "L1") (pin "1") (pinfunction "1_1") (pintype "passive"))
      (node (ref "U3") (pin "2") (pinfunction "SW_2") (pintype "passive"))
    )
    (net (code "61") (name "Net-(U11-OUTH)") (class "Default")
      (node (ref "R20") (pin "2") (pinfunction "2_2") (pintype "passive"))
      (node (ref "U11") (pin "2") (pinfunction "OUTH_2") (pintype "passive"))
    )
    (net (code "62") (name "Net-(U11-OUTL)") (class "Default")
      (node (ref "R21") (pin "2") (pinfunction "2_2") (pintype "passive"))
      (node (ref "U11") (pin "3") (pinfunction "OUTL_3") (pintype "passive"))
    )
    (net (code "63") (name "VBUS") (class "Default")
      (node (ref "C6") (pin "2") (pinfunction "2_2") (pintype "passive"))
      (node (ref "Q1") (pin "5") (pinfunction "D_5") (pintype "passive"))
      (node (ref "Q1") (pin "6") (pinfunction "D_6") (pintype "passive"))
      (node (ref "Q1") (pin "7") (pinfunction "D_7") (pintype "passive"))
      (node (ref "Q1") (pin "8") (pinfunction "D_8") (pintype "passive"))
      (node (ref "R6") (pin "2") (pinfunction "2_2") (pintype "passive"))
      (node (ref "U2") (pin "2") (pinfunction "VIN_2") (pintype "passive"))
      (node (ref "USB1") (pin "A9") (pinfunction "VBUS_A9") (pintype "passive"))
      (node (ref "USB1") (pin "B9") (pinfunction "VBUS_B9") (pintype "passive"))
    )
    (net (code "64") (name "unconnected-(U2-NC-Pad3)") (class "Default")
      (node (ref "U2") (pin "3") (pinfunction "NC_3") (pintype "passive+no_connect"))
    )
    (net (code "65") (name "unconnected-(U2-NC-Pad4)") (class "Default")
      (node (ref "U2") (pin "4") (pinfunction "NC_4") (pintype "passive+no_connect"))
    )
    (net (code "66") (name "unconnected-(U2-NC-Pad9)") (class "Default")
      (node (ref "U2") (pin "9") (pinfunction "NC_9") (pintype "passive+no_connect"))
    )
    (net (code "67") (name "unconnected-(U2-NC-Pad10)") (class "Default")
      (node (ref "U2") (pin "10") (pinfunction "NC_10") (pintype "passive+no_connect"))
    )
    (net (code "68") (name "unconnected-(U2-NC-Pad14)") (class "Default")
      (node (ref "U2") (pin "14") (pinfunction "NC_14") (pintype "passive+no_connect"))
    )
    (net (code "69") (name "unconnected-(U2-NC-Pad15)") (class "Default")
      (node (ref "U2") (pin "15") (pinfunction "NC_15") (pintype "passive+no_connect"))
    )
    (net (code "70") (name "unconnected-(U2-TST1-Pad6)") (class "Default")
      (node (ref "U2") (pin "6") (pinfunction "TST1_6") (pintype "passive+no_connect"))
    )
    (net (code "71") (name "unconnected-(U2-TST2-Pad7)") (class "Default")
      (node (ref "U2") (pin "7") (pinfunction "TST2_7") (pintype "passive+no_connect"))
    )
    (net (code "72") (name "unconnected-(U2-TST3-Pad8)") (class "Default")
      (node (ref "U2") (pin "8") (pinfunction "TST3_8") (pintype "passive+no_connect"))
    )
    (net (code "73") (name "unconnected-(U2-VBUS-Pad16)") (class "Default")
      (node (ref "U2") (pin "16") (pinfunction "VBUS_16") (pintype "passive"))
    )
    (net (code "74") (name "unconnected-(X1-Pad16)") (class "Default")
      (node (ref "X1") (pin "16") (pinfunction "16_16") (pintype "passive+no_connect"))
    )
    (net (code "75") (name "unconnected-(X1-Pad17)") (class "Default")
      (node (ref "X1") (pin "17") (pinfunction "17_17") (pintype "passive+no_connect"))
    )
  )
)
